# dengenn.net
KiCad netlist of a schematic drawn in EAGLE
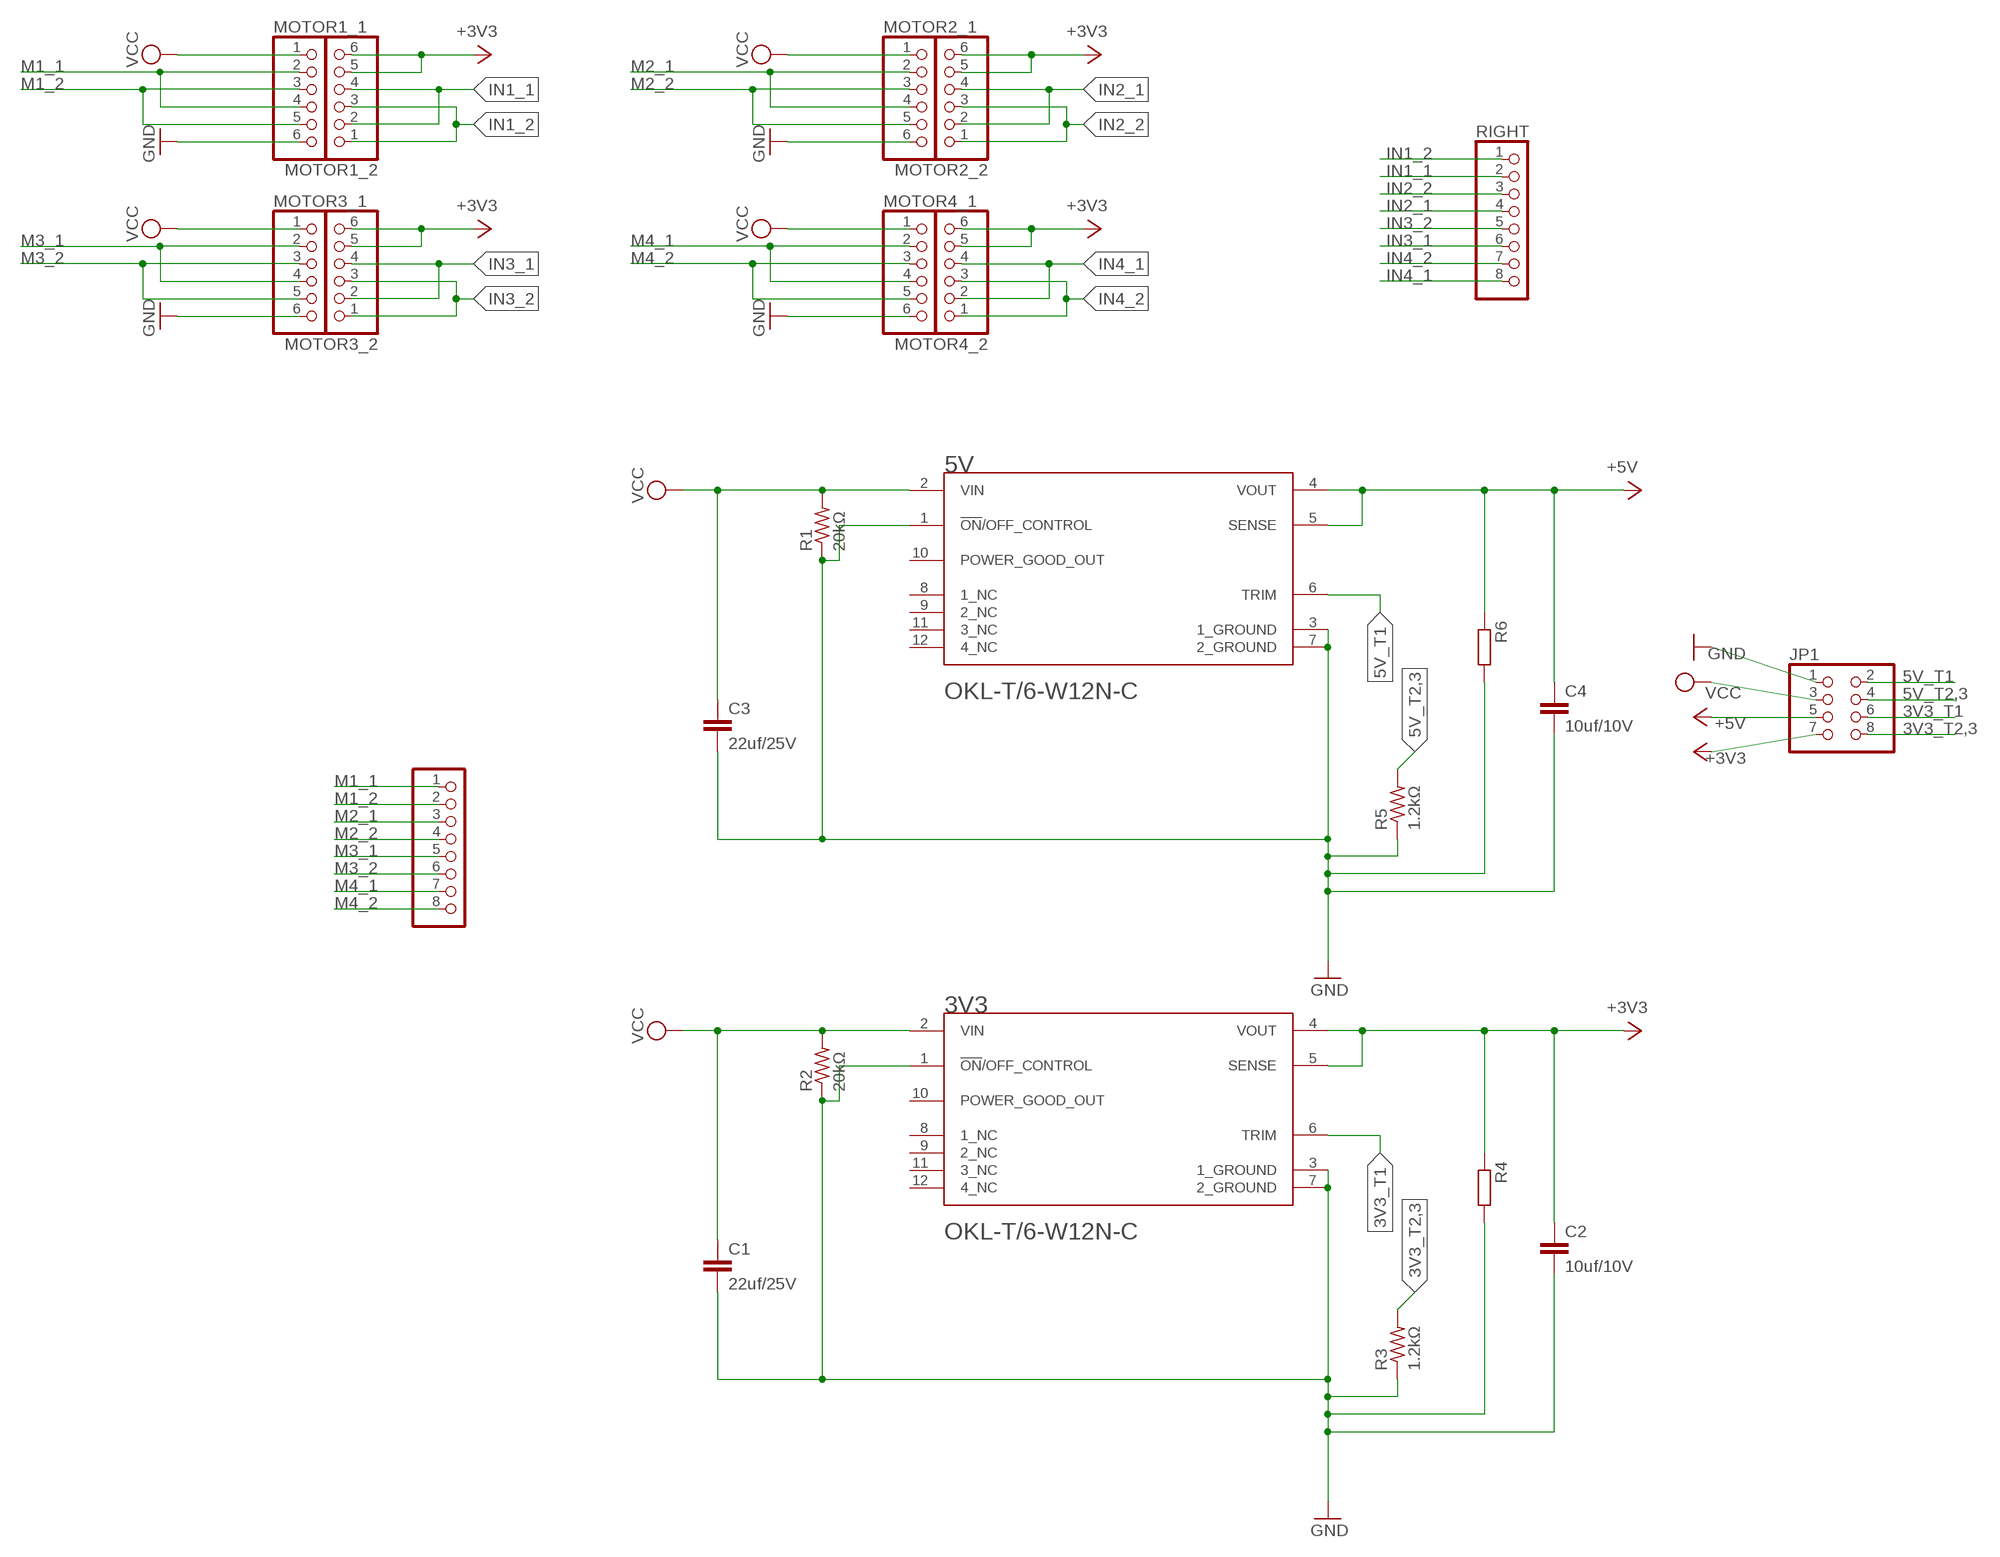
[diagram p0: schematic, sheet 1]

(export (version "E")
  (design (tool "Eeschema 10.0.6"))
  (components
    (comp (ref "3V3")
      (value "OKL-T/6-W12N-CMURATA_OKL-T-6-W12N-C_0_0")
      (footprint "eagle-import:MURATA_OKL-T-6-W12N-C_0")
      (fields (field (name "MF") "Murata Power Solutions Inc.") (field (name "MP") "OKL-T/6-W12N-C"))
      (libsource (lib "eagle-import") (part "OKL-T/6-W12N-CMURATA_OKL-T-6-W12N-C_0_0"))
    )
    (comp (ref "5V")
      (value "OKL-T/6-W12N-CMURATA_OKL-T-6-W12N-C_0_0")
      (footprint "eagle-import:MURATA_OKL-T-6-W12N-C_0")
      (fields (field (name "MF") "Murata Power Solutions Inc.") (field (name "MP") "OKL-T/6-W12N-C"))
      (libsource (lib "eagle-import") (part "OKL-T/6-W12N-CMURATA_OKL-T-6-W12N-C_0_0"))
    )
    (comp (ref "C1")
      (value "22uf/25V")
      (footprint "eagle-import:C1206")
      (libsource (lib "eagle-import") (part "C-EUC1206"))
    )
    (comp (ref "C2")
      (value "10uf/10V")
      (footprint "eagle-import:C0603")
      (libsource (lib "eagle-import") (part "C-EUC0603"))
    )
    (comp (ref "C3")
      (value "22uf/25V")
      (footprint "eagle-import:C1206")
      (libsource (lib "eagle-import") (part "C-EUC1206"))
    )
    (comp (ref "C4")
      (value "10uf/10V")
      (footprint "eagle-import:C0603")
      (libsource (lib "eagle-import") (part "C-EUC0603"))
    )
    (comp (ref "JP1")
      (value "PINHD-2X4")
      (footprint "eagle-import:2X04")
      (libsource (lib "eagle-import") (part "PINHD-2X4"))
    )
    (comp (ref "LEFT")
      (value "PINHD-1X8")
      (footprint "eagle-import:1X08")
      (libsource (lib "eagle-import") (part "PINHD-1X8"))
    )
    (comp (ref "MOTOR1_1")
      (value "PINHD-1X06_2.54-S")
      (footprint "eagle-import:1X06-S")
      (libsource (lib "eagle-import") (part "PINHD-1X06_2.54-S"))
    )
    (comp (ref "MOTOR1_2")
      (value "PINHD-1X06_2.54-S")
      (footprint "eagle-import:1X06-S")
      (libsource (lib "eagle-import") (part "PINHD-1X06_2.54-S"))
    )
    (comp (ref "MOTOR2_1")
      (value "PINHD-1X06_2.54-S")
      (footprint "eagle-import:1X06-S")
      (libsource (lib "eagle-import") (part "PINHD-1X06_2.54-S"))
    )
    (comp (ref "MOTOR2_2")
      (value "PINHD-1X06_2.54-S")
      (footprint "eagle-import:1X06-S")
      (libsource (lib "eagle-import") (part "PINHD-1X06_2.54-S"))
    )
    (comp (ref "MOTOR3_1")
      (value "PINHD-1X06_2.54-S")
      (footprint "eagle-import:1X06-S")
      (libsource (lib "eagle-import") (part "PINHD-1X06_2.54-S"))
    )
    (comp (ref "MOTOR3_2")
      (value "PINHD-1X06_2.54-S")
      (footprint "eagle-import:1X06-S")
      (libsource (lib "eagle-import") (part "PINHD-1X06_2.54-S"))
    )
    (comp (ref "MOTOR4_1")
      (value "PINHD-1X06_2.54-S")
      (footprint "eagle-import:1X06-S")
      (libsource (lib "eagle-import") (part "PINHD-1X06_2.54-S"))
    )
    (comp (ref "MOTOR4_2")
      (value "PINHD-1X06_2.54-S")
      (footprint "eagle-import:1X06-S")
      (libsource (lib "eagle-import") (part "PINHD-1X06_2.54-S"))
    )
    (comp (ref "R1")
      (value "20kΩ")
      (footprint "eagle-import:R0603")
      (libsource (lib "eagle-import") (part "R-US_R0603"))
    )
    (comp (ref "R2")
      (value "20kΩ")
      (footprint "eagle-import:R0603")
      (libsource (lib "eagle-import") (part "R-US_R0603"))
    )
    (comp (ref "R3")
      (value "1.2kΩ")
      (footprint "eagle-import:R0603")
      (libsource (lib "eagle-import") (part "R-US_R0603"))
    )
    (comp (ref "R4")
      (value "R-EU_0309/12")
      (footprint "eagle-import:0309_12")
      (libsource (lib "eagle-import") (part "R-EU_0309/12"))
    )
    (comp (ref "R5")
      (value "1.2kΩ")
      (footprint "eagle-import:R0603")
      (libsource (lib "eagle-import") (part "R-US_R0603"))
    )
    (comp (ref "R6")
      (value "R-EU_0309/12")
      (footprint "eagle-import:0309_12")
      (libsource (lib "eagle-import") (part "R-EU_0309/12"))
    )
    (comp (ref "RIGHT")
      (value "PINHD-1X8")
      (footprint "eagle-import:1X08")
      (libsource (lib "eagle-import") (part "PINHD-1X8"))
    )
  )
  (nets
    (net (code "1") (name "+3V3") (class "Default")
      (node (ref "3V3") (pin "4") (pinfunction "VOUT_4") (pintype "bidirectional"))
      (node (ref "3V3") (pin "5") (pinfunction "SENSE_5") (pintype "passive"))
      (node (ref "C2") (pin "1") (pinfunction "1_1") (pintype "passive"))
      (node (ref "JP1") (pin "7") (pinfunction "7_7") (pintype "passive"))
      (node (ref "MOTOR1_2") (pin "5") (pinfunction "5_5") (pintype "passive"))
      (node (ref "MOTOR1_2") (pin "6") (pinfunction "6_6") (pintype "passive"))
      (node (ref "MOTOR2_2") (pin "5") (pinfunction "5_5") (pintype "passive"))
      (node (ref "MOTOR2_2") (pin "6") (pinfunction "6_6") (pintype "passive"))
      (node (ref "MOTOR3_2") (pin "5") (pinfunction "5_5") (pintype "passive"))
      (node (ref "MOTOR3_2") (pin "6") (pinfunction "6_6") (pintype "passive"))
      (node (ref "MOTOR4_2") (pin "5") (pinfunction "5_5") (pintype "passive"))
      (node (ref "MOTOR4_2") (pin "6") (pinfunction "6_6") (pintype "passive"))
      (node (ref "R4") (pin "1") (pinfunction "1_1") (pintype "passive"))
    )
    (net (code "2") (name "+5V") (class "Default")
      (node (ref "5V") (pin "4") (pinfunction "VOUT_4") (pintype "bidirectional"))
      (node (ref "5V") (pin "5") (pinfunction "SENSE_5") (pintype "passive"))
      (node (ref "C4") (pin "1") (pinfunction "1_1") (pintype "passive"))
      (node (ref "JP1") (pin "5") (pinfunction "5_5") (pintype "passive"))
      (node (ref "R6") (pin "1") (pinfunction "1_1") (pintype "passive"))
    )
    (net (code "3") (name "/M1_1") (class "Default")
      (node (ref "LEFT") (pin "1") (pinfunction "1_1") (pintype "passive"))
      (node (ref "MOTOR1_1") (pin "2") (pinfunction "2_2") (pintype "passive"))
      (node (ref "MOTOR1_1") (pin "4") (pinfunction "4_4") (pintype "passive"))
    )
    (net (code "4") (name "/M1_2") (class "Default")
      (node (ref "LEFT") (pin "2") (pinfunction "2_2") (pintype "passive"))
      (node (ref "MOTOR1_1") (pin "3") (pinfunction "3_3") (pintype "passive"))
      (node (ref "MOTOR1_1") (pin "5") (pinfunction "5_5") (pintype "passive"))
    )
    (net (code "5") (name "/M2_1") (class "Default")
      (node (ref "LEFT") (pin "3") (pinfunction "3_3") (pintype "passive"))
      (node (ref "MOTOR2_1") (pin "2") (pinfunction "2_2") (pintype "passive"))
      (node (ref "MOTOR2_1") (pin "4") (pinfunction "4_4") (pintype "passive"))
    )
    (net (code "6") (name "/M2_2") (class "Default")
      (node (ref "LEFT") (pin "4") (pinfunction "4_4") (pintype "passive"))
      (node (ref "MOTOR2_1") (pin "3") (pinfunction "3_3") (pintype "passive"))
      (node (ref "MOTOR2_1") (pin "5") (pinfunction "5_5") (pintype "passive"))
    )
    (net (code "7") (name "/M3_1") (class "Default")
      (node (ref "LEFT") (pin "5") (pinfunction "5_5") (pintype "passive"))
      (node (ref "MOTOR3_1") (pin "2") (pinfunction "2_2") (pintype "passive"))
      (node (ref "MOTOR3_1") (pin "4") (pinfunction "4_4") (pintype "passive"))
    )
    (net (code "8") (name "/M3_2") (class "Default")
      (node (ref "LEFT") (pin "6") (pinfunction "6_6") (pintype "passive"))
      (node (ref "MOTOR3_1") (pin "3") (pinfunction "3_3") (pintype "passive"))
      (node (ref "MOTOR3_1") (pin "5") (pinfunction "5_5") (pintype "passive"))
    )
    (net (code "9") (name "/M4_1") (class "Default")
      (node (ref "LEFT") (pin "7") (pinfunction "7_7") (pintype "passive"))
      (node (ref "MOTOR4_1") (pin "2") (pinfunction "2_2") (pintype "passive"))
      (node (ref "MOTOR4_1") (pin "4") (pinfunction "4_4") (pintype "passive"))
    )
    (net (code "10") (name "/M4_2") (class "Default")
      (node (ref "LEFT") (pin "8") (pinfunction "8_8") (pintype "passive"))
      (node (ref "MOTOR4_1") (pin "3") (pinfunction "3_3") (pintype "passive"))
      (node (ref "MOTOR4_1") (pin "5") (pinfunction "5_5") (pintype "passive"))
    )
    (net (code "11") (name "3V3_T1") (class "Default")
      (node (ref "3V3") (pin "6") (pinfunction "TRIM_6") (pintype "passive"))
      (node (ref "JP1") (pin "6") (pinfunction "6_6") (pintype "passive"))
    )
    (net (code "12") (name "3V3_T2,3") (class "Default")
      (node (ref "JP1") (pin "8") (pinfunction "8_8") (pintype "passive"))
      (node (ref "R3") (pin "2") (pinfunction "2_2") (pintype "passive"))
    )
    (net (code "13") (name "5V_T1") (class "Default")
      (node (ref "5V") (pin "6") (pinfunction "TRIM_6") (pintype "passive"))
      (node (ref "JP1") (pin "2") (pinfunction "2_2") (pintype "passive"))
    )
    (net (code "14") (name "5V_T2,3") (class "Default")
      (node (ref "JP1") (pin "4") (pinfunction "4_4") (pintype "passive"))
      (node (ref "R5") (pin "2") (pinfunction "2_2") (pintype "passive"))
    )
    (net (code "15") (name "GND") (class "Default")
      (node (ref "3V3") (pin "1") (pinfunction "~{ON}/OFF_CONTROL_1") (pintype "bidirectional"))
      (node (ref "3V3") (pin "3") (pinfunction "1_GROUND_3") (pintype "power_in"))
      (node (ref "3V3") (pin "7") (pinfunction "2_GROUND_7") (pintype "power_in"))
      (node (ref "5V") (pin "1") (pinfunction "~{ON}/OFF_CONTROL_1") (pintype "bidirectional"))
      (node (ref "5V") (pin "3") (pinfunction "1_GROUND_3") (pintype "power_in"))
      (node (ref "5V") (pin "7") (pinfunction "2_GROUND_7") (pintype "power_in"))
      (node (ref "C1") (pin "2") (pinfunction "2_2") (pintype "passive"))
      (node (ref "C2") (pin "2") (pinfunction "2_2") (pintype "passive"))
      (node (ref "C3") (pin "2") (pinfunction "2_2") (pintype "passive"))
      (node (ref "C4") (pin "2") (pinfunction "2_2") (pintype "passive"))
      (node (ref "JP1") (pin "1") (pinfunction "1_1") (pintype "passive"))
      (node (ref "MOTOR1_1") (pin "6") (pinfunction "6_6") (pintype "passive"))
      (node (ref "MOTOR2_1") (pin "6") (pinfunction "6_6") (pintype "passive"))
      (node (ref "MOTOR3_1") (pin "6") (pinfunction "6_6") (pintype "passive"))
      (node (ref "MOTOR4_1") (pin "6") (pinfunction "6_6") (pintype "passive"))
      (node (ref "R1") (pin "1") (pinfunction "1_1") (pintype "passive"))
      (node (ref "R2") (pin "1") (pinfunction "1_1") (pintype "passive"))
      (node (ref "R3") (pin "1") (pinfunction "1_1") (pintype "passive"))
      (node (ref "R4") (pin "2") (pinfunction "2_2") (pintype "passive"))
      (node (ref "R5") (pin "1") (pinfunction "1_1") (pintype "passive"))
      (node (ref "R6") (pin "2") (pinfunction "2_2") (pintype "passive"))
    )
    (net (code "16") (name "IN1_1") (class "Default")
      (node (ref "MOTOR1_2") (pin "2") (pinfunction "2_2") (pintype "passive"))
      (node (ref "MOTOR1_2") (pin "4") (pinfunction "4_4") (pintype "passive"))
      (node (ref "RIGHT") (pin "2") (pinfunction "2_2") (pintype "passive"))
    )
    (net (code "17") (name "IN1_2") (class "Default")
      (node (ref "MOTOR1_2") (pin "1") (pinfunction "1_1") (pintype "passive"))
      (node (ref "MOTOR1_2") (pin "3") (pinfunction "3_3") (pintype "passive"))
      (node (ref "RIGHT") (pin "1") (pinfunction "1_1") (pintype "passive"))
    )
    (net (code "18") (name "IN2_1") (class "Default")
      (node (ref "MOTOR2_2") (pin "2") (pinfunction "2_2") (pintype "passive"))
      (node (ref "MOTOR2_2") (pin "4") (pinfunction "4_4") (pintype "passive"))
      (node (ref "RIGHT") (pin "4") (pinfunction "4_4") (pintype "passive"))
    )
    (net (code "19") (name "IN2_2") (class "Default")
      (node (ref "MOTOR2_2") (pin "1") (pinfunction "1_1") (pintype "passive"))
      (node (ref "MOTOR2_2") (pin "3") (pinfunction "3_3") (pintype "passive"))
      (node (ref "RIGHT") (pin "3") (pinfunction "3_3") (pintype "passive"))
    )
    (net (code "20") (name "IN3_1") (class "Default")
      (node (ref "MOTOR3_2") (pin "2") (pinfunction "2_2") (pintype "passive"))
      (node (ref "MOTOR3_2") (pin "4") (pinfunction "4_4") (pintype "passive"))
      (node (ref "RIGHT") (pin "6") (pinfunction "6_6") (pintype "passive"))
    )
    (net (code "21") (name "IN3_2") (class "Default")
      (node (ref "MOTOR3_2") (pin "1") (pinfunction "1_1") (pintype "passive"))
      (node (ref "MOTOR3_2") (pin "3") (pinfunction "3_3") (pintype "passive"))
      (node (ref "RIGHT") (pin "5") (pinfunction "5_5") (pintype "passive"))
    )
    (net (code "22") (name "IN4_1") (class "Default")
      (node (ref "MOTOR4_2") (pin "2") (pinfunction "2_2") (pintype "passive"))
      (node (ref "MOTOR4_2") (pin "4") (pinfunction "4_4") (pintype "passive"))
      (node (ref "RIGHT") (pin "8") (pinfunction "8_8") (pintype "passive"))
    )
    (net (code "23") (name "IN4_2") (class "Default")
      (node (ref "MOTOR4_2") (pin "1") (pinfunction "1_1") (pintype "passive"))
      (node (ref "MOTOR4_2") (pin "3") (pinfunction "3_3") (pintype "passive"))
      (node (ref "RIGHT") (pin "7") (pinfunction "7_7") (pintype "passive"))
    )
    (net (code "24") (name "VCC") (class "Default")
      (node (ref "3V3") (pin "2") (pinfunction "VIN_2") (pintype "bidirectional"))
      (node (ref "5V") (pin "2") (pinfunction "VIN_2") (pintype "bidirectional"))
      (node (ref "C1") (pin "1") (pinfunction "1_1") (pintype "passive"))
      (node (ref "C3") (pin "1") (pinfunction "1_1") (pintype "passive"))
      (node (ref "JP1") (pin "3") (pinfunction "3_3") (pintype "passive"))
      (node (ref "MOTOR1_1") (pin "1") (pinfunction "1_1") (pintype "passive"))
      (node (ref "MOTOR2_1") (pin "1") (pinfunction "1_1") (pintype "passive"))
      (node (ref "MOTOR3_1") (pin "1") (pinfunction "1_1") (pintype "passive"))
      (node (ref "MOTOR4_1") (pin "1") (pinfunction "1_1") (pintype "passive"))
      (node (ref "R1") (pin "2") (pinfunction "2_2") (pintype "passive"))
      (node (ref "R2") (pin "2") (pinfunction "2_2") (pintype "passive"))
    )
    (net (code "25") (name "unconnected-(3V3-1_NC-Pad8)") (class "Default")
      (node (ref "3V3") (pin "8") (pinfunction "1_NC_8") (pintype "passive"))
    )
    (net (code "26") (name "unconnected-(3V3-2_NC-Pad9)") (class "Default")
      (node (ref "3V3") (pin "9") (pinfunction "2_NC_9") (pintype "passive"))
    )
    (net (code "27") (name "unconnected-(3V3-3_NC-Pad11)") (class "Default")
      (node (ref "3V3") (pin "11") (pinfunction "3_NC_11") (pintype "passive"))
    )
    (net (code "28") (name "unconnected-(3V3-4_NC-Pad12)") (class "Default")
      (node (ref "3V3") (pin "12") (pinfunction "4_NC_12") (pintype "passive"))
    )
    (net (code "29") (name "unconnected-(3V3-POWER_GOOD_OUT-Pad10)") (class "Default")
      (node (ref "3V3") (pin "10") (pinfunction "POWER_GOOD_OUT_10") (pintype "open_collector"))
    )
    (net (code "30") (name "unconnected-(5V-1_NC-Pad8)") (class "Default")
      (node (ref "5V") (pin "8") (pinfunction "1_NC_8") (pintype "passive"))
    )
    (net (code "31") (name "unconnected-(5V-2_NC-Pad9)") (class "Default")
      (node (ref "5V") (pin "9") (pinfunction "2_NC_9") (pintype "passive"))
    )
    (net (code "32") (name "unconnected-(5V-3_NC-Pad11)") (class "Default")
      (node (ref "5V") (pin "11") (pinfunction "3_NC_11") (pintype "passive"))
    )
    (net (code "33") (name "unconnected-(5V-4_NC-Pad12)") (class "Default")
      (node (ref "5V") (pin "12") (pinfunction "4_NC_12") (pintype "passive"))
    )
    (net (code "34") (name "unconnected-(5V-POWER_GOOD_OUT-Pad10)") (class "Default")
      (node (ref "5V") (pin "10") (pinfunction "POWER_GOOD_OUT_10") (pintype "open_collector"))
    )
  )
)
